# esp8266.net
KiCad netlist of a schematic drawn in EAGLE
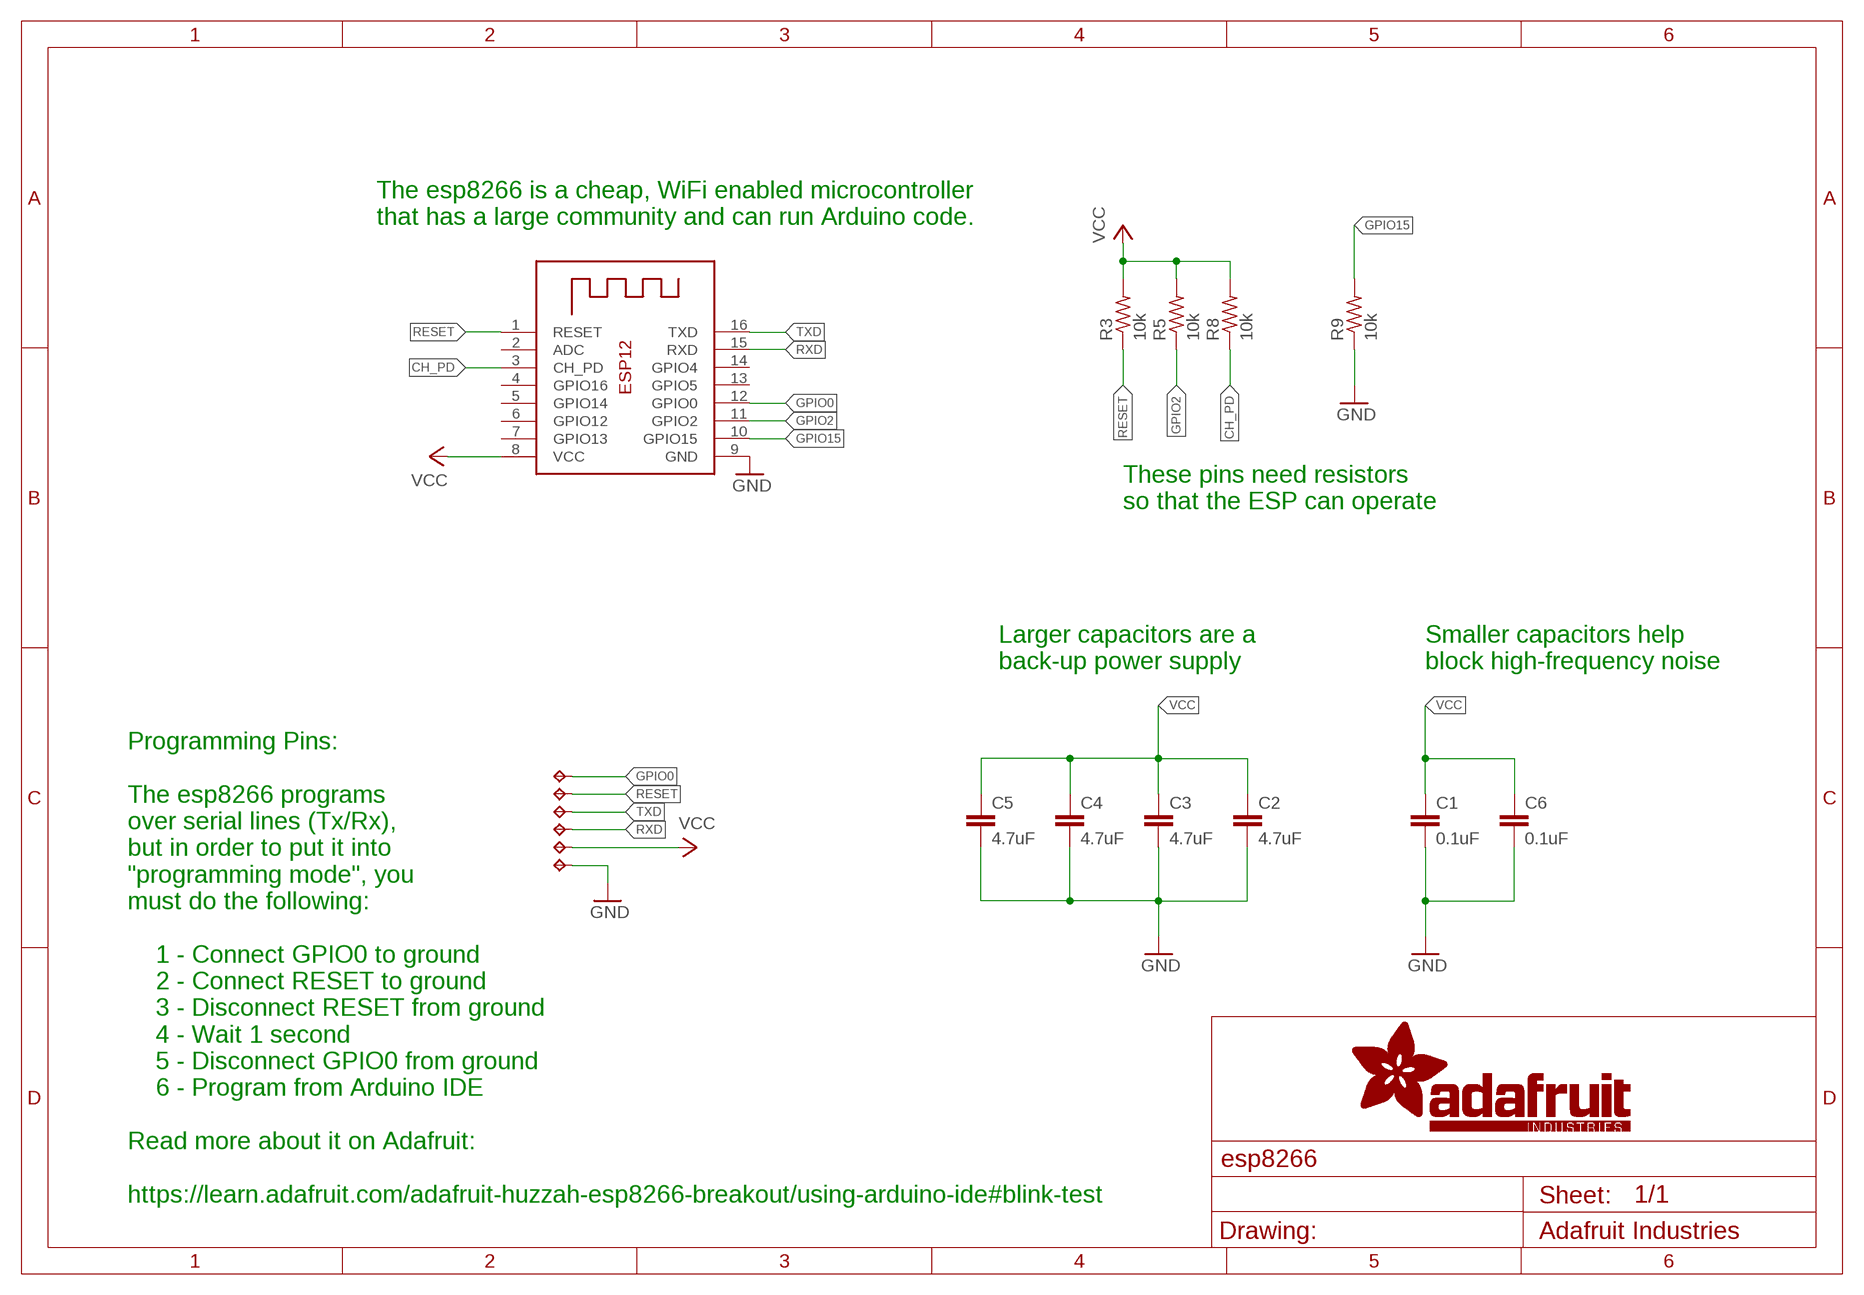
[diagram p0: schematic, sheet 1]

(export (version "E")
  (design (tool "Eeschema 10.0.6"))
  (components
    (comp (ref "C1")
      (value "0.1uF")
      (footprint "eagle-import:0603")
      (libsource (lib "eagle-import") (part "0.1UF-0603-25V-5%"))
    )
    (comp (ref "C2")
      (value "4.7uF")
      (footprint "eagle-import:0603")
      (libsource (lib "eagle-import") (part "4.7UF0603"))
    )
    (comp (ref "C3")
      (value "4.7uF")
      (footprint "eagle-import:0603")
      (libsource (lib "eagle-import") (part "4.7UF0603"))
    )
    (comp (ref "C4")
      (value "4.7uF")
      (footprint "eagle-import:0603")
      (libsource (lib "eagle-import") (part "4.7UF0603"))
    )
    (comp (ref "C5")
      (value "4.7uF")
      (footprint "eagle-import:0603")
      (libsource (lib "eagle-import") (part "4.7UF0603"))
    )
    (comp (ref "C6")
      (value "0.1uF")
      (footprint "eagle-import:0603")
      (libsource (lib "eagle-import") (part "0.1UF-0603-25V-5%"))
    )
    (comp (ref "GND")
      (value "TPTP20R")
      (footprint "eagle-import:TP20R")
      (libsource (lib "eagle-import") (part "TPTP20R"))
    )
    (comp (ref "GPIO0")
      (value "TPTP20R")
      (footprint "eagle-import:TP20R")
      (libsource (lib "eagle-import") (part "TPTP20R"))
    )
    (comp (ref "R3")
      (value "10k")
      (footprint "eagle-import:R0603")
      (libsource (lib "eagle-import") (part "R-US_R0603"))
    )
    (comp (ref "R5")
      (value "10k")
      (footprint "eagle-import:R0603")
      (libsource (lib "eagle-import") (part "R-US_R0603"))
    )
    (comp (ref "R8")
      (value "10k")
      (footprint "eagle-import:R0603")
      (libsource (lib "eagle-import") (part "R-US_R0603"))
    )
    (comp (ref "R9")
      (value "10k")
      (footprint "eagle-import:R0603")
      (libsource (lib "eagle-import") (part "R-US_R0603"))
    )
    (comp (ref "RESET")
      (value "TPTP20R")
      (footprint "eagle-import:TP20R")
      (libsource (lib "eagle-import") (part "TPTP20R"))
    )
    (comp (ref "RX")
      (value "TPTP20R")
      (footprint "eagle-import:TP20R")
      (libsource (lib "eagle-import") (part "TPTP20R"))
    )
    (comp (ref "TX")
      (value "TPTP20R")
      (footprint "eagle-import:TP20R")
      (libsource (lib "eagle-import") (part "TPTP20R"))
    )
    (comp (ref "VCC")
      (value "TPTP20R")
      (footprint "eagle-import:TP20R")
      (libsource (lib "eagle-import") (part "TPTP20R"))
    )
    (comp (ref "X1")
      (value "ESP-12")
      (footprint "eagle-import:ESP-12")
      (libsource (lib "eagle-import") (part "ESP-12"))
    )
  )
  (nets
    (net (code "1") (name "CH_PD") (class "Default")
      (node (ref "R8") (pin "1") (pinfunction "1_1") (pintype "passive"))
      (node (ref "X1") (pin "3") (pinfunction "CH_PD_3") (pintype "input"))
    )
    (net (code "2") (name "GND") (class "Default")
      (node (ref "C1") (pin "2") (pinfunction "2_2") (pintype "passive"))
      (node (ref "C2") (pin "2") (pinfunction "2_2") (pintype "passive"))
      (node (ref "C3") (pin "2") (pinfunction "2_2") (pintype "passive"))
      (node (ref "C4") (pin "2") (pinfunction "2_2") (pintype "passive"))
      (node (ref "C5") (pin "2") (pinfunction "2_2") (pintype "passive"))
      (node (ref "C6") (pin "2") (pinfunction "2_2") (pintype "passive"))
      (node (ref "GND") (pin "TP") (pinfunction "TP_TP") (pintype "input"))
      (node (ref "R9") (pin "1") (pinfunction "1_1") (pintype "passive"))
      (node (ref "X1") (pin "9") (pinfunction "GND_9") (pintype "power_in"))
    )
    (net (code "3") (name "GPIO0") (class "Default")
      (node (ref "GPIO0") (pin "TP") (pinfunction "TP_TP") (pintype "input"))
      (node (ref "X1") (pin "12") (pinfunction "GPIO0_12") (pintype "bidirectional"))
    )
    (net (code "4") (name "GPIO2") (class "Default")
      (node (ref "R5") (pin "1") (pinfunction "1_1") (pintype "passive"))
      (node (ref "X1") (pin "11") (pinfunction "GPIO2_11") (pintype "bidirectional"))
    )
    (net (code "5") (name "GPIO15") (class "Default")
      (node (ref "R9") (pin "2") (pinfunction "2_2") (pintype "passive"))
      (node (ref "X1") (pin "10") (pinfunction "GPIO15_10") (pintype "bidirectional"))
    )
    (net (code "6") (name "RESET") (class "Default")
      (node (ref "R3") (pin "1") (pinfunction "1_1") (pintype "passive"))
      (node (ref "RESET") (pin "TP") (pinfunction "TP_TP") (pintype "input"))
      (node (ref "X1") (pin "1") (pinfunction "RESET_1") (pintype "input"))
    )
    (net (code "7") (name "RXD") (class "Default")
      (node (ref "RX") (pin "TP") (pinfunction "TP_TP") (pintype "input"))
      (node (ref "X1") (pin "15") (pinfunction "RXD_15") (pintype "input"))
    )
    (net (code "8") (name "TXD") (class "Default")
      (node (ref "TX") (pin "TP") (pinfunction "TP_TP") (pintype "input"))
      (node (ref "X1") (pin "16") (pinfunction "TXD_16") (pintype "output"))
    )
    (net (code "9") (name "VCC") (class "Default")
      (node (ref "C1") (pin "1") (pinfunction "1_1") (pintype "passive"))
      (node (ref "C2") (pin "1") (pinfunction "1_1") (pintype "passive"))
      (node (ref "C3") (pin "1") (pinfunction "1_1") (pintype "passive"))
      (node (ref "C4") (pin "1") (pinfunction "1_1") (pintype "passive"))
      (node (ref "C5") (pin "1") (pinfunction "1_1") (pintype "passive"))
      (node (ref "C6") (pin "1") (pinfunction "1_1") (pintype "passive"))
      (node (ref "R3") (pin "2") (pinfunction "2_2") (pintype "passive"))
      (node (ref "R5") (pin "2") (pinfunction "2_2") (pintype "passive"))
      (node (ref "R8") (pin "2") (pinfunction "2_2") (pintype "passive"))
      (node (ref "VCC") (pin "TP") (pinfunction "TP_TP") (pintype "input"))
      (node (ref "X1") (pin "8") (pinfunction "VCC_8") (pintype "power_in"))
    )
    (net (code "10") (name "unconnected-(X1-ADC-Pad2)") (class "Default")
      (node (ref "X1") (pin "2") (pinfunction "ADC_2") (pintype "passive"))
    )
    (net (code "11") (name "unconnected-(X1-GPIO4-Pad14)") (class "Default")
      (node (ref "X1") (pin "14") (pinfunction "GPIO4_14") (pintype "bidirectional"))
    )
    (net (code "12") (name "unconnected-(X1-GPIO5-Pad13)") (class "Default")
      (node (ref "X1") (pin "13") (pinfunction "GPIO5_13") (pintype "bidirectional"))
    )
    (net (code "13") (name "unconnected-(X1-GPIO12-Pad6)") (class "Default")
      (node (ref "X1") (pin "6") (pinfunction "GPIO12_6") (pintype "bidirectional"))
    )
    (net (code "14") (name "unconnected-(X1-GPIO13-Pad7)") (class "Default")
      (node (ref "X1") (pin "7") (pinfunction "GPIO13_7") (pintype "bidirectional"))
    )
    (net (code "15") (name "unconnected-(X1-GPIO14-Pad5)") (class "Default")
      (node (ref "X1") (pin "5") (pinfunction "GPIO14_5") (pintype "bidirectional"))
    )
    (net (code "16") (name "unconnected-(X1-GPIO16-Pad4)") (class "Default")
      (node (ref "X1") (pin "4") (pinfunction "GPIO16_4") (pintype "bidirectional"))
    )
  )
)
